# Triac_x4.net
KiCad netlist of a schematic drawn in EAGLE
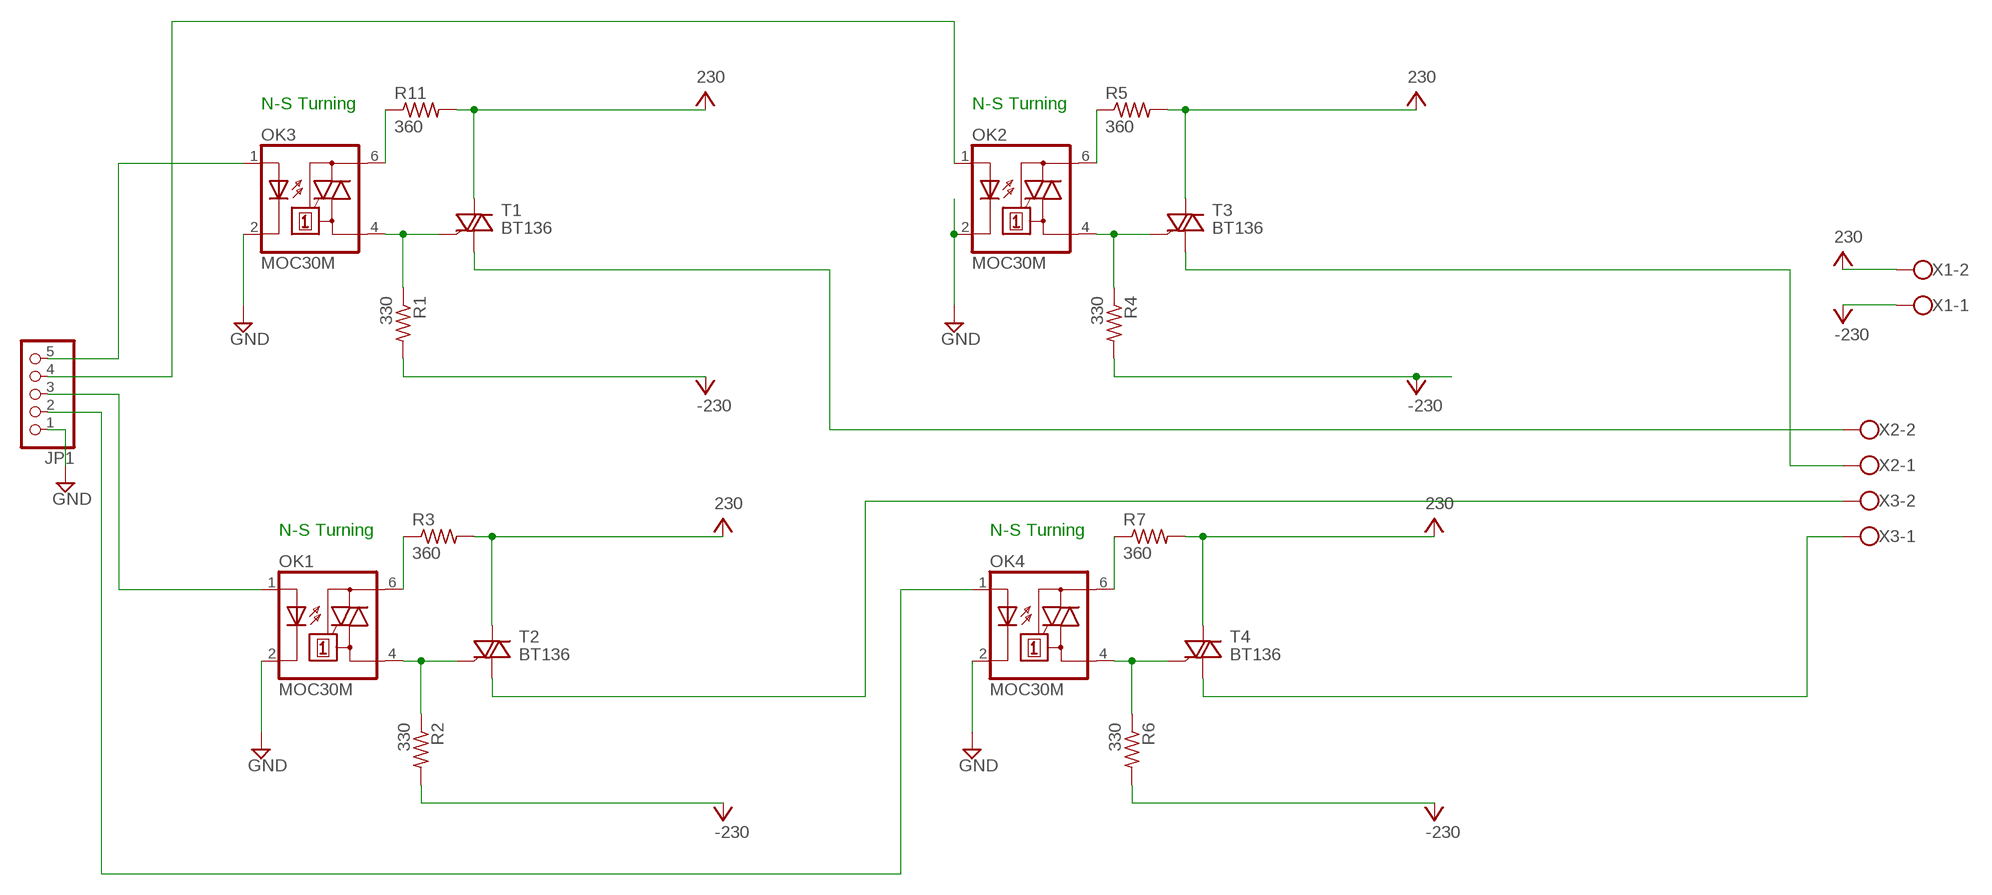
[diagram p0: schematic, sheet 1]

(export (version "E")
  (design (tool "Eeschema 10.0.6"))
  (components
    (comp (ref "JP1")
      (value "PINHD-1X5")
      (footprint "eagle-import:1X05")
      (libsource (lib "eagle-import") (part "PINHD-1X5"))
    )
    (comp (ref "OK1")
      (value "MOC30M")
      (footprint "eagle-import:DIL06")
      (fields (field (name "MF") "FAIRCHILD SEMICONDUCTOR") (field (name "MPN") "MOC3023-M"))
      (libsource (lib "eagle-import") (part "MOC30M23"))
    )
    (comp (ref "OK2")
      (value "MOC30M")
      (footprint "eagle-import:DIL06")
      (fields (field (name "MF") "FAIRCHILD SEMICONDUCTOR") (field (name "MPN") "MOC3023-M"))
      (libsource (lib "eagle-import") (part "MOC30M23"))
    )
    (comp (ref "OK3")
      (value "MOC30M")
      (footprint "eagle-import:DIL06")
      (fields (field (name "MF") "FAIRCHILD SEMICONDUCTOR") (field (name "MPN") "MOC3023-M"))
      (libsource (lib "eagle-import") (part "MOC30M23"))
    )
    (comp (ref "OK4")
      (value "MOC30M")
      (footprint "eagle-import:DIL06")
      (fields (field (name "MF") "FAIRCHILD SEMICONDUCTOR") (field (name "MPN") "MOC3023-M"))
      (libsource (lib "eagle-import") (part "MOC30M23"))
    )
    (comp (ref "R1")
      (value "330")
      (footprint "eagle-import:0207_7")
      (libsource (lib "eagle-import") (part "R-US_0207/7"))
    )
    (comp (ref "R2")
      (value "330")
      (footprint "eagle-import:0207_7")
      (libsource (lib "eagle-import") (part "R-US_0207/7"))
    )
    (comp (ref "R3")
      (value "360")
      (footprint "eagle-import:0207_7")
      (libsource (lib "eagle-import") (part "R-US_0207/7"))
    )
    (comp (ref "R4")
      (value "330")
      (footprint "eagle-import:0207_7")
      (libsource (lib "eagle-import") (part "R-US_0207/7"))
    )
    (comp (ref "R5")
      (value "360")
      (footprint "eagle-import:0207_7")
      (libsource (lib "eagle-import") (part "R-US_0207/7"))
    )
    (comp (ref "R6")
      (value "330")
      (footprint "eagle-import:0207_7")
      (libsource (lib "eagle-import") (part "R-US_0207/7"))
    )
    (comp (ref "R7")
      (value "360")
      (footprint "eagle-import:0207_7")
      (libsource (lib "eagle-import") (part "R-US_0207/7"))
    )
    (comp (ref "R11")
      (value "360")
      (footprint "eagle-import:0207_7")
      (libsource (lib "eagle-import") (part "R-US_0207/7"))
    )
    (comp (ref "T1")
      (value "BT136")
      (footprint "eagle-import:TO220AB")
      (libsource (lib "eagle-import") (part "BT136"))
    )
    (comp (ref "T2")
      (value "BT136")
      (footprint "eagle-import:TO220AB")
      (libsource (lib "eagle-import") (part "BT136"))
    )
    (comp (ref "T3")
      (value "BT136")
      (footprint "eagle-import:TO220AB")
      (libsource (lib "eagle-import") (part "BT136"))
    )
    (comp (ref "T4")
      (value "BT136")
      (footprint "eagle-import:TO220AB")
      (libsource (lib "eagle-import") (part "BT136"))
    )
    (comp (ref "X1")
      (value "W237-102")
      (footprint "eagle-import:W237-102")
      (fields (field (name "MPN") "237-102"))
      (libsource (lib "eagle-import") (part "W237-102"))
    )
    (comp (ref "X2")
      (value "W237-102")
      (footprint "eagle-import:W237-102")
      (fields (field (name "MPN") "237-102"))
      (libsource (lib "eagle-import") (part "W237-102"))
    )
    (comp (ref "X3")
      (value "W237-102")
      (footprint "eagle-import:W237-102")
      (fields (field (name "MPN") "237-102"))
      (libsource (lib "eagle-import") (part "W237-102"))
    )
  )
  (nets
    (net (code "1") (name "-230") (class "Default")
      (node (ref "R1") (pin "2") (pinfunction "2_2") (pintype "passive"))
      (node (ref "R2") (pin "2") (pinfunction "2_2") (pintype "passive"))
      (node (ref "R4") (pin "2") (pinfunction "2_2") (pintype "passive"))
      (node (ref "R6") (pin "2") (pinfunction "2_2") (pintype "passive"))
      (node (ref "X1") (pin "1") (pinfunction "KL_1") (pintype "passive"))
    )
    (net (code "2") (name "230") (class "Default")
      (node (ref "R11") (pin "2") (pinfunction "2_2") (pintype "passive"))
      (node (ref "R3") (pin "2") (pinfunction "2_2") (pintype "passive"))
      (node (ref "R5") (pin "2") (pinfunction "2_2") (pintype "passive"))
      (node (ref "R7") (pin "2") (pinfunction "2_2") (pintype "passive"))
      (node (ref "T1") (pin "2") (pinfunction "A2_2") (pintype "passive"))
      (node (ref "T2") (pin "2") (pinfunction "A2_2") (pintype "passive"))
      (node (ref "T3") (pin "2") (pinfunction "A2_2") (pintype "passive"))
      (node (ref "T4") (pin "2") (pinfunction "A2_2") (pintype "passive"))
      (node (ref "X1") (pin "2") (pinfunction "KL_2") (pintype "passive"))
    )
    (net (code "3") (name "GND") (class "Default")
      (node (ref "JP1") (pin "1") (pinfunction "1_1") (pintype "passive"))
      (node (ref "OK1") (pin "2") (pinfunction "C_2") (pintype "passive"))
      (node (ref "OK2") (pin "2") (pinfunction "C_2") (pintype "passive"))
      (node (ref "OK3") (pin "2") (pinfunction "C_2") (pintype "passive"))
      (node (ref "OK4") (pin "2") (pinfunction "C_2") (pintype "passive"))
    )
    (net (code "4") (name "Net-(OK1-A)") (class "Default")
      (node (ref "JP1") (pin "3") (pinfunction "3_3") (pintype "passive"))
      (node (ref "OK1") (pin "1") (pinfunction "A_1") (pintype "passive"))
    )
    (net (code "5") (name "Net-(OK1-A1)") (class "Default")
      (node (ref "OK1") (pin "4") (pinfunction "A1_4") (pintype "passive"))
      (node (ref "R2") (pin "1") (pinfunction "1_1") (pintype "passive"))
      (node (ref "T2") (pin "3") (pinfunction "G_3") (pintype "passive"))
    )
    (net (code "6") (name "Net-(OK1-A2)") (class "Default")
      (node (ref "OK1") (pin "6") (pinfunction "A2_6") (pintype "passive"))
      (node (ref "R3") (pin "1") (pinfunction "1_1") (pintype "passive"))
    )
    (net (code "7") (name "Net-(OK2-A)") (class "Default")
      (node (ref "JP1") (pin "4") (pinfunction "4_4") (pintype "passive"))
      (node (ref "OK2") (pin "1") (pinfunction "A_1") (pintype "passive"))
    )
    (net (code "8") (name "Net-(OK2-A1)") (class "Default")
      (node (ref "OK2") (pin "4") (pinfunction "A1_4") (pintype "passive"))
      (node (ref "R4") (pin "1") (pinfunction "1_1") (pintype "passive"))
      (node (ref "T3") (pin "3") (pinfunction "G_3") (pintype "passive"))
    )
    (net (code "9") (name "Net-(OK2-A2)") (class "Default")
      (node (ref "OK2") (pin "6") (pinfunction "A2_6") (pintype "passive"))
      (node (ref "R5") (pin "1") (pinfunction "1_1") (pintype "passive"))
    )
    (net (code "10") (name "Net-(OK3-A)") (class "Default")
      (node (ref "JP1") (pin "5") (pinfunction "5_5") (pintype "passive"))
      (node (ref "OK3") (pin "1") (pinfunction "A_1") (pintype "passive"))
    )
    (net (code "11") (name "Net-(OK3-A1)") (class "Default")
      (node (ref "OK3") (pin "4") (pinfunction "A1_4") (pintype "passive"))
      (node (ref "R1") (pin "1") (pinfunction "1_1") (pintype "passive"))
      (node (ref "T1") (pin "3") (pinfunction "G_3") (pintype "passive"))
    )
    (net (code "12") (name "Net-(OK3-A2)") (class "Default")
      (node (ref "OK3") (pin "6") (pinfunction "A2_6") (pintype "passive"))
      (node (ref "R11") (pin "1") (pinfunction "1_1") (pintype "passive"))
    )
    (net (code "13") (name "Net-(OK4-A)") (class "Default")
      (node (ref "JP1") (pin "2") (pinfunction "2_2") (pintype "passive"))
      (node (ref "OK4") (pin "1") (pinfunction "A_1") (pintype "passive"))
    )
    (net (code "14") (name "Net-(OK4-A1)") (class "Default")
      (node (ref "OK4") (pin "4") (pinfunction "A1_4") (pintype "passive"))
      (node (ref "R6") (pin "1") (pinfunction "1_1") (pintype "passive"))
      (node (ref "T4") (pin "3") (pinfunction "G_3") (pintype "passive"))
    )
    (net (code "15") (name "Net-(OK4-A2)") (class "Default")
      (node (ref "OK4") (pin "6") (pinfunction "A2_6") (pintype "passive"))
      (node (ref "R7") (pin "1") (pinfunction "1_1") (pintype "passive"))
    )
    (net (code "16") (name "Net-(T1-A1)") (class "Default")
      (node (ref "T1") (pin "1") (pinfunction "A1_1") (pintype "passive"))
      (node (ref "X2") (pin "2") (pinfunction "KL_2") (pintype "passive"))
    )
    (net (code "17") (name "Net-(T2-A1)") (class "Default")
      (node (ref "T2") (pin "1") (pinfunction "A1_1") (pintype "passive"))
      (node (ref "X3") (pin "2") (pinfunction "KL_2") (pintype "passive"))
    )
    (net (code "18") (name "Net-(T3-A1)") (class "Default")
      (node (ref "T3") (pin "1") (pinfunction "A1_1") (pintype "passive"))
      (node (ref "X2") (pin "1") (pinfunction "KL_1") (pintype "passive"))
    )
    (net (code "19") (name "Net-(T4-A1)") (class "Default")
      (node (ref "T4") (pin "1") (pinfunction "A1_1") (pintype "passive"))
      (node (ref "X3") (pin "1") (pinfunction "KL_1") (pintype "passive"))
    )
  )
)
